# PTFV_PWR_PMIC.net
KiCad netlist of a schematic drawn in Altium Designer
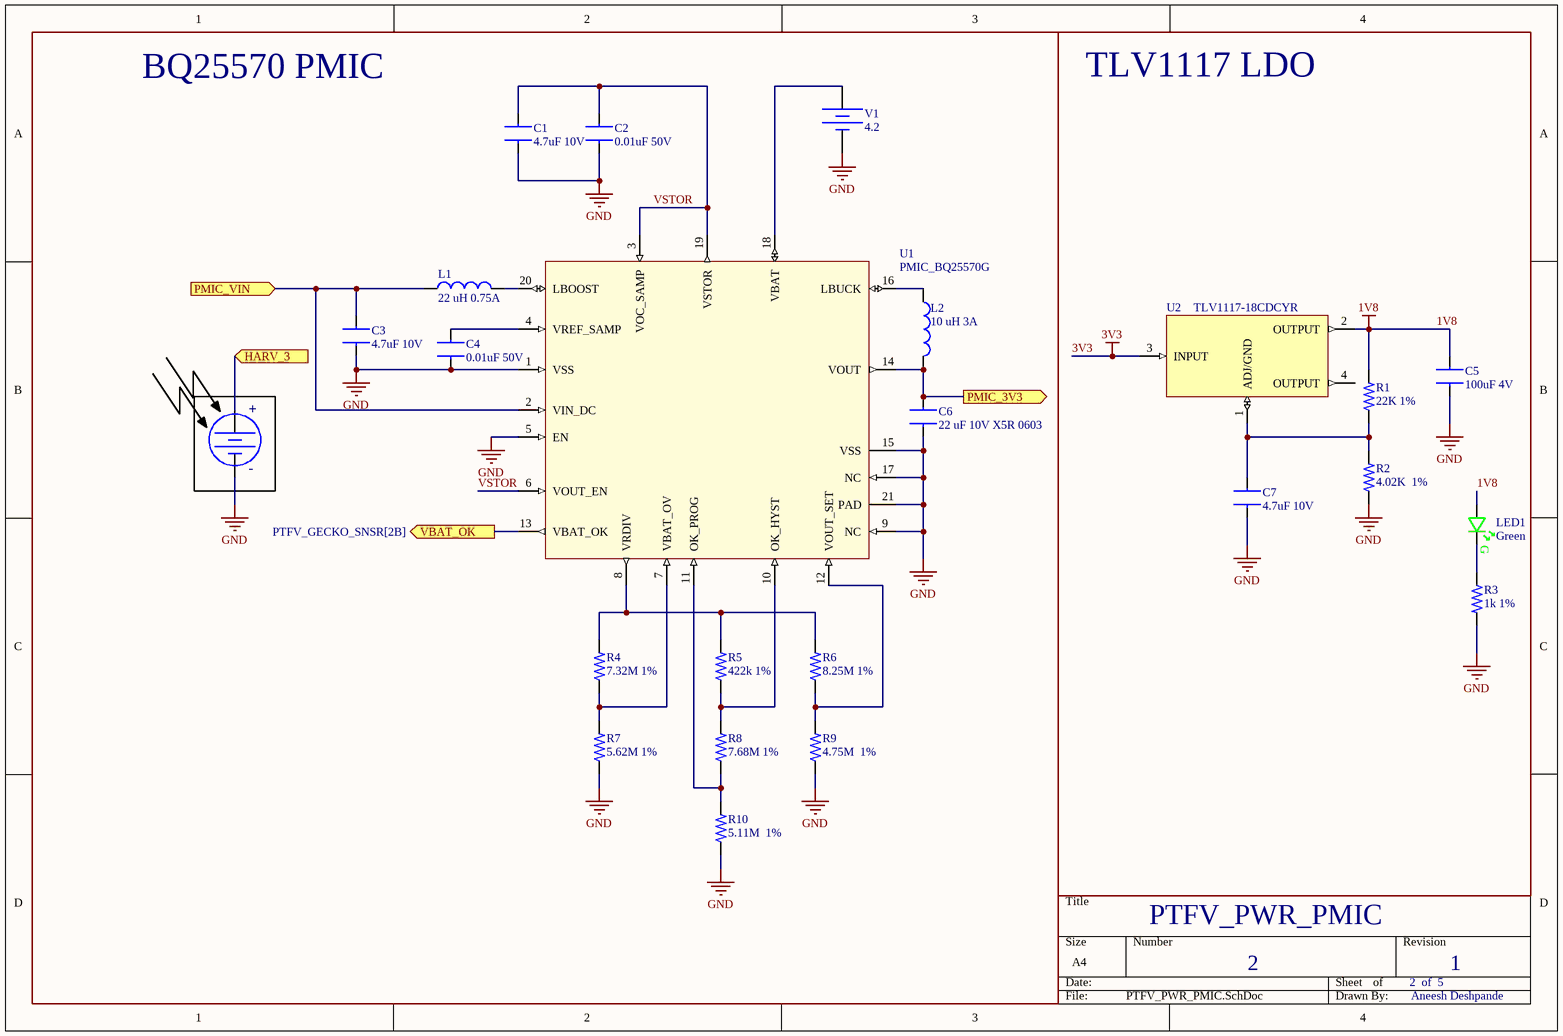
[diagram p0: PTFV_PWR_PMIC.SchDoc]

(export (version "E")
  (design (tool "Eeschema 10.0.6"))
  (components
    (comp (ref "C1")
      (value "4.7uF 10V")
      (footprint "CAP_0603_1MM")
      (description "CAP CER 4.7UF 10V X5R 0603")
      (fields
        (field (name "MANUFACTURER") "Samsung")
        (field (name "MANUFACTURER PART NUMBER") "CL10A475KP8NNNC")
      )
      (libsource (lib "LPEDT_Parts") (part "CL10A475KP8NNNC"))
    )
    (comp (ref "C2")
      (value "0.01uF 50V")
      (footprint "CAP_0603_1MM")
      (description "CAP CER 0.01uF 50V X7R 0603")
      (fields
        (field (name "MANUFACTURER") "Yageo")
        (field (name "MANUFACTURER PART NUMBER") "CC0603KRX7R9BB103")
      )
      (libsource (lib "LPEDT_Parts") (part "CC0603KRX7R9BB103"))
    )
    (comp (ref "C3")
      (value "4.7uF 10V")
      (footprint "CAP_0603_1MM")
      (description "CAP CER 4.7UF 10V X5R 0603")
      (fields
        (field (name "MANUFACTURER") "Samsung")
        (field (name "MANUFACTURER PART NUMBER") "CL10A475KP8NNNC")
      )
      (libsource (lib "LPEDT_Parts") (part "CL10A475KP8NNNC"))
    )
    (comp (ref "C4")
      (value "0.01uF 50V")
      (footprint "CAP_0603_1MM")
      (description "CAP CER 0.01uF 50V X7R 0603")
      (fields
        (field (name "MANUFACTURER") "Yageo")
        (field (name "MANUFACTURER PART NUMBER") "CC0603KRX7R9BB103")
      )
      (libsource (lib "LPEDT_Parts") (part "CC0603KRX7R9BB103"))
    )
    (comp (ref "C5")
      (value "100uF 4V")
      (footprint "CAP_0603_1MM")
      (description "CAP TANT 100uF \r\n4V 0603")
      (fields
        (field (name "MANUFACTURER") "Vishay Sprague")
        (field (name "MANUFACTURER PART NUMBER") "298W107X0004M2T")
      )
      (libsource (lib "LPEDT_Parts_Library") (part "298W107X0004M2T"))
    )
    (comp (ref "C6")
      (value "22 uF 10V X5R 0603")
      (footprint "CAP_0603_1MM")
      (description "CAP CER 22UF 10V X5R 0603")
      (fields
        (field (name "MANUFACTURER") "Murata")
        (field (name "MANUFACTURER PART NUMBER") "GRM188R61A226ME15D")
      )
      (libsource (lib "LPEDT_Parts_Library") (part "GRM188R61A226ME15D"))
    )
    (comp (ref "C7")
      (value "4.7uF 10V")
      (footprint "CAP_0603_1MM")
      (description "CAP CER 4.7UF 10V X5R 0603")
      (fields
        (field (name "MANUFACTURER") "Samsung")
        (field (name "MANUFACTURER PART NUMBER") "CL10A475KP8NNNC")
      )
      (libsource (lib "LPEDT_Parts_Library") (part "CL10A475KP8NNNC"))
    )
    (comp (ref "L1")
      (value "22 uH 0.75A")
      (footprint "IND_2828x30")
      (description "IND FER 22uH 20% SMD")
      (fields
        (field (name "MANUFACTURER") "Wurth Electronics")
        (field (name "MANUFACTURER PART NUMBER") "744025220")
      )
      (libsource (lib "LPEDT_Parts_Library") (part "744025220"))
    )
    (comp (ref "L2")
      (value "10 uH 3A")
      (footprint "IND_100X30")
      (description "IND FER 10uH 20% SMD")
      (fields
        (field (name "MANUFACTURER") "Wurth Electronics")
        (field (name "MANUFACTURER PART NUMBER") "744065100")
      )
      (libsource (lib "LPEDT_Parts_Library") (part "744065100"))
    )
    (comp (ref "LED1")
      (value "Green")
      (footprint "LED_0603_GRN_WL-SMCW")
      (description "LED, 0603, GREEN, 430MCD, 520NM")
      (fields
        (field (name "MANUFACTURER") "Wurth Electronics")
        (field (name "MANUFACTURER PART NUMBER") "150060GS75000")
      )
      (libsource (lib "LPEDT_Parts_Library") (part "150060GS75000"))
    )
    (comp (ref "R1")
      (value "22K 1%")
      (footprint "RES_0603_1608X06")
      (description "RES SMD 22K OHM 1% 1/10W 0603")
      (fields
        (field (name "MANUFACTURER") "Yageo")
        (field (name "MANUFACTURER PART NUMBER") "RC0603JR-0722KL")
      )
      (libsource (lib "LPEDT_Parts_Library") (part "RC0603JR-0722KL"))
    )
    (comp (ref "R2")
      (value "4.02K  1%")
      (footprint "RES_0603_1608X06")
      (description "RES SMD 4.02K OHM 1% 1/10W 0603")
      (fields
        (field (name "MANUFACTURER") "Yageo")
        (field (name "MANUFACTURER PART NUMBER") "RC0603FR-074K02L")
      )
      (libsource (lib "LPEDT_Parts_Library") (part "RC0603FR-074K02L"))
    )
    (comp (ref "R3")
      (value "1k 1%")
      (footprint "RES_0603_1608X06")
      (description "RES SMD 1k OHM 1% 1/10W 0603")
      (fields
        (field (name "MANUFACTURER") "Yageo")
        (field (name "MANUFACTURER PART NUMBER") "RC0603FR-071KL")
      )
      (libsource (lib "LPEDT_Parts_Library") (part "RC0603FR-071KL"))
    )
    (comp (ref "R4")
      (value "7.32M 1%")
      (footprint "RES_0603_1608X06")
      (description "RES SMD 7.32M OHM 1% 1/10W 0603")
      (fields
        (field (name "MANUFACTURER") "Vishay")
        (field (name "MANUFACTURER PART NUMBER") "CRCW06037M32FKEA")
      )
      (libsource (lib "LPEDT_Parts_Library") (part "CRCW06037M32FKEA"))
    )
    (comp (ref "R5")
      (value "422k 1%")
      (footprint "RES_0603_1608X06")
      (description "RES SMD 422k OHM 1% 1/10W 0603")
      (fields
        (field (name "MANUFACTURER") "Yageo")
        (field (name "MANUFACTURER PART NUMBER") "RC0603FR-07422KL")
      )
      (libsource (lib "LPEDT_Parts_Library") (part "RC0603FR-07422KL"))
    )
    (comp (ref "R6")
      (value "8.25M 1%")
      (footprint "RES_0603_1608X06")
      (description "RES SMD 8.25M OHM 1% 1/10W 0603")
      (fields
        (field (name "MANUFACTURER") "Vishay")
        (field (name "MANUFACTURER PART NUMBER") "CRCW06038M25FKEA")
      )
      (libsource (lib "LPEDT_Parts_Library") (part "CRCW06038M25FKEA"))
    )
    (comp (ref "R7")
      (value "5.62M 1%")
      (footprint "RES_0603_1608X06")
      (description "RES SMD 5.62M OHM 1% 1/10W 0603")
      (fields
        (field (name "MANUFACTURER") "Stackpole Electronics")
        (field (name "MANUFACTURER PART NUMBER") "RMCF0603FT5M62")
      )
      (libsource (lib "LPEDT_Parts_Library") (part "RMCF0603FT5M62"))
    )
    (comp (ref "R8")
      (value "7.68M 1%")
      (footprint "RES_0603_1608X06")
      (description "RES SMD 7.68M OHM 1% 1/10W 0603")
      (fields
        (field (name "MANUFACTURER") "Stackpole Electronics")
        (field (name "MANUFACTURER PART NUMBER") "RMCF0603FT7M68")
      )
      (libsource (lib "LPEDT_Parts_Library") (part "RMCF0603FT7M68"))
    )
    (comp (ref "R9")
      (value "4.75M  1%")
      (footprint "RES_0603_1608X06")
      (description "RES SMD 4.75M OHM 1% 1/10W 0603")
      (fields
        (field (name "MANUFACTURER") "Yageo")
        (field (name "MANUFACTURER PART NUMBER") "RC0603FR-074M75L")
      )
      (libsource (lib "LPEDT_Parts_Library") (part "RC0603FR-074M75L"))
    )
    (comp (ref "R10")
      (value "5.11M  1%")
      (footprint "RES_0603_1608X06")
      (description "RES SMD 5.11M OHM 1% 1/10W 0603")
      (fields
        (field (name "MANUFACTURER") "Yageo")
        (field (name "MANUFACTURER PART NUMBER") "RC0603FR-075M11L")
      )
      (libsource (lib "LPEDT_Parts_Library") (part "RC0603FR-075M11L"))
    )
    (comp (ref "U1")
      (value "PMIC_BQ25570G")
      (footprint "20_QFN_PMIC")
      (description "IC ENERGY HARV CTRLR BATT 20VQFN")
      (fields
        (field (name "MANUFACTURER") "Texas Instruments")
        (field (name "MANUFACTURER PART NUMBER") "BQ25570RGRR")
      )
      (libsource (lib "LPEDT_Parts") (part "BQ25570RGRR"))
    )
    (comp (ref "U2")
      (value "TLV1117-18CDCYR")
      (footprint "SOT23_4_LDO")
      (description "LDO 1.8V")
      (fields (field (name "MANUFACTURER") "Texas Instruments"))
      (libsource (lib "LPEDT_Parts_Library") (part "TLV1117-18CDCYR"))
    )
    (comp (ref "V1")
      (value "Constant Voltage Source")
      (fields (field (name "DC MAGNITUDE") "4.2"))
      (libsource (lib "Simulation Generic Components") (part "Battery"))
    )
    (comp (ref "V2")
      (value "Constant Voltage Source")
      (libsource (lib "Simulation Generic Components") (part "Battery"))
    )
  )
  (nets
    (net (code "1") (name "/HARV_3") (class "Default")
      (node (ref "V2") (pin "1") (pinfunction "1_1") (pintype "passive"))
    )
    (net (code "2") (name "/PMIC_3V3") (class "Default")
      (node (ref "C6") (pin "1") (pinfunction "1_1") (pintype "passive"))
      (node (ref "L2") (pin "2") (pinfunction "2_2") (pintype "passive"))
      (node (ref "U1") (pin "14") (pinfunction "VOUT_14") (pintype "output"))
    )
    (net (code "3") (name "/PMIC_VIN") (class "Default")
      (node (ref "C3") (pin "1") (pinfunction "1_1") (pintype "passive"))
      (node (ref "L1") (pin "1") (pinfunction "1_1") (pintype "passive"))
      (node (ref "U1") (pin "2") (pinfunction "VIN_DC_2") (pintype "input"))
    )
    (net (code "4") (name "/VBAT_OK") (class "Default")
      (node (ref "U1") (pin "13") (pinfunction "VBAT_OK_13") (pintype "output"))
    )
    (net (code "5") (name "/VSTOR") (class "Default")
      (node (ref "C1") (pin "1") (pinfunction "1_1") (pintype "passive"))
      (node (ref "C2") (pin "1") (pinfunction "1_1") (pintype "passive"))
      (node (ref "U1") (pin "19") (pinfunction "VSTOR_19") (pintype "output"))
      (node (ref "U1") (pin "3") (pinfunction "VOC_SAMP_3") (pintype "input"))
      (node (ref "U1") (pin "6") (pinfunction "VOUT_EN_6") (pintype "input"))
    )
    (net (code "6") (name "1V8") (class "Default")
      (node (ref "C5") (pin "1") (pinfunction "1_1") (pintype "passive"))
      (node (ref "LED1") (pin "A") (pinfunction "A_A") (pintype "passive"))
      (node (ref "R1") (pin "2") (pinfunction "2_2") (pintype "passive"))
      (node (ref "U2") (pin "2") (pinfunction "OUTPUT_2") (pintype "output"))
    )
    (net (code "7") (name "3V3") (class "Default")
      (node (ref "U2") (pin "3") (pinfunction "INPUT_3") (pintype "input"))
    )
    (net (code "8") (name "GND") (class "Default")
      (node (ref "C1") (pin "2") (pinfunction "2_2") (pintype "passive"))
      (node (ref "C2") (pin "2") (pinfunction "2_2") (pintype "passive"))
      (node (ref "C3") (pin "2") (pinfunction "2_2") (pintype "passive"))
      (node (ref "C4") (pin "2") (pinfunction "2_2") (pintype "passive"))
      (node (ref "C5") (pin "2") (pinfunction "2_2") (pintype "passive"))
      (node (ref "C6") (pin "2") (pinfunction "2_2") (pintype "passive"))
      (node (ref "C7") (pin "2") (pinfunction "2_2") (pintype "passive"))
      (node (ref "R10") (pin "1") (pinfunction "1_1") (pintype "passive"))
      (node (ref "R2") (pin "1") (pinfunction "1_1") (pintype "passive"))
      (node (ref "R3") (pin "2") (pinfunction "2_2") (pintype "passive"))
      (node (ref "R7") (pin "1") (pinfunction "1_1") (pintype "passive"))
      (node (ref "R9") (pin "1") (pinfunction "1_1") (pintype "passive"))
      (node (ref "U1") (pin "1") (pinfunction "VSS_1") (pintype "input"))
      (node (ref "U1") (pin "15") (pinfunction "VSS_15") (pintype "passive"))
      (node (ref "U1") (pin "17") (pinfunction "NC_17") (pintype "input"))
      (node (ref "U1") (pin "21") (pinfunction "PAD_21") (pintype "passive"))
      (node (ref "U1") (pin "5") (pinfunction "EN_5") (pintype "input"))
      (node (ref "U1") (pin "9") (pinfunction "NC_9") (pintype "input"))
      (node (ref "V1") (pin "2") (pinfunction "2_2") (pintype "passive"))
      (node (ref "V2") (pin "2") (pinfunction "2_2") (pintype "passive"))
    )
    (net (code "9") (name "Net-(LED1-PadC)") (class "Default")
      (node (ref "LED1") (pin "C") (pinfunction "C_C") (pintype "passive"))
      (node (ref "R3") (pin "1") (pinfunction "1_1") (pintype "passive"))
    )
    (net (code "10") (name "Net-(U1-LBOOST)") (class "Default")
      (node (ref "L1") (pin "2") (pinfunction "2_2") (pintype "passive"))
      (node (ref "U1") (pin "20") (pinfunction "LBOOST_20") (pintype "bidirectional"))
    )
    (net (code "11") (name "Net-(U1-LBUCK)") (class "Default")
      (node (ref "L2") (pin "1") (pinfunction "1_1") (pintype "passive"))
      (node (ref "U1") (pin "16") (pinfunction "LBUCK_16") (pintype "bidirectional"))
    )
    (net (code "12") (name "Net-(U1-OK_HYST)") (class "Default")
      (node (ref "R5") (pin "1") (pinfunction "1_1") (pintype "passive"))
      (node (ref "R8") (pin "2") (pinfunction "2_2") (pintype "passive"))
      (node (ref "U1") (pin "10") (pinfunction "OK_HYST_10") (pintype "input"))
    )
    (net (code "13") (name "Net-(U1-OK_PROG)") (class "Default")
      (node (ref "R10") (pin "2") (pinfunction "2_2") (pintype "passive"))
      (node (ref "R8") (pin "1") (pinfunction "1_1") (pintype "passive"))
      (node (ref "U1") (pin "11") (pinfunction "OK_PROG_11") (pintype "input"))
    )
    (net (code "14") (name "Net-(U1-VBAT)") (class "Default")
      (node (ref "U1") (pin "18") (pinfunction "VBAT_18") (pintype "bidirectional"))
      (node (ref "V1") (pin "1") (pinfunction "1_1") (pintype "passive"))
    )
    (net (code "15") (name "Net-(U1-VBAT_OV)") (class "Default")
      (node (ref "R4") (pin "1") (pinfunction "1_1") (pintype "passive"))
      (node (ref "R7") (pin "2") (pinfunction "2_2") (pintype "passive"))
      (node (ref "U1") (pin "7") (pinfunction "VBAT_OV_7") (pintype "input"))
    )
    (net (code "16") (name "Net-(U1-VOUT_SET)") (class "Default")
      (node (ref "R6") (pin "1") (pinfunction "1_1") (pintype "passive"))
      (node (ref "R9") (pin "2") (pinfunction "2_2") (pintype "passive"))
      (node (ref "U1") (pin "12") (pinfunction "VOUT_SET_12") (pintype "input"))
    )
    (net (code "17") (name "Net-(U1-VRDIV)") (class "Default")
      (node (ref "R4") (pin "2") (pinfunction "2_2") (pintype "passive"))
      (node (ref "R5") (pin "2") (pinfunction "2_2") (pintype "passive"))
      (node (ref "R6") (pin "2") (pinfunction "2_2") (pintype "passive"))
      (node (ref "U1") (pin "8") (pinfunction "VRDIV_8") (pintype "output"))
    )
    (net (code "18") (name "Net-(U1-VREF_SAMP)") (class "Default")
      (node (ref "C4") (pin "1") (pinfunction "1_1") (pintype "passive"))
      (node (ref "U1") (pin "4") (pinfunction "VREF_SAMP_4") (pintype "input"))
    )
    (net (code "19") (name "Net-(U2-ADJ{slash}GND)") (class "Default")
      (node (ref "C7") (pin "1") (pinfunction "1_1") (pintype "passive"))
      (node (ref "R1") (pin "1") (pinfunction "1_1") (pintype "passive"))
      (node (ref "R2") (pin "2") (pinfunction "2_2") (pintype "passive"))
      (node (ref "U2") (pin "1") (pinfunction "ADJ/GND_1") (pintype "bidirectional"))
    )
    (net (code "20") (name "unconnected-(U2-OUTPUT-Pad4)") (class "Default")
      (node (ref "U2") (pin "4") (pinfunction "OUTPUT_4") (pintype "output"))
    )
  )
)
